# freeDSP.net
KiCad netlist of a schematic drawn in EAGLE
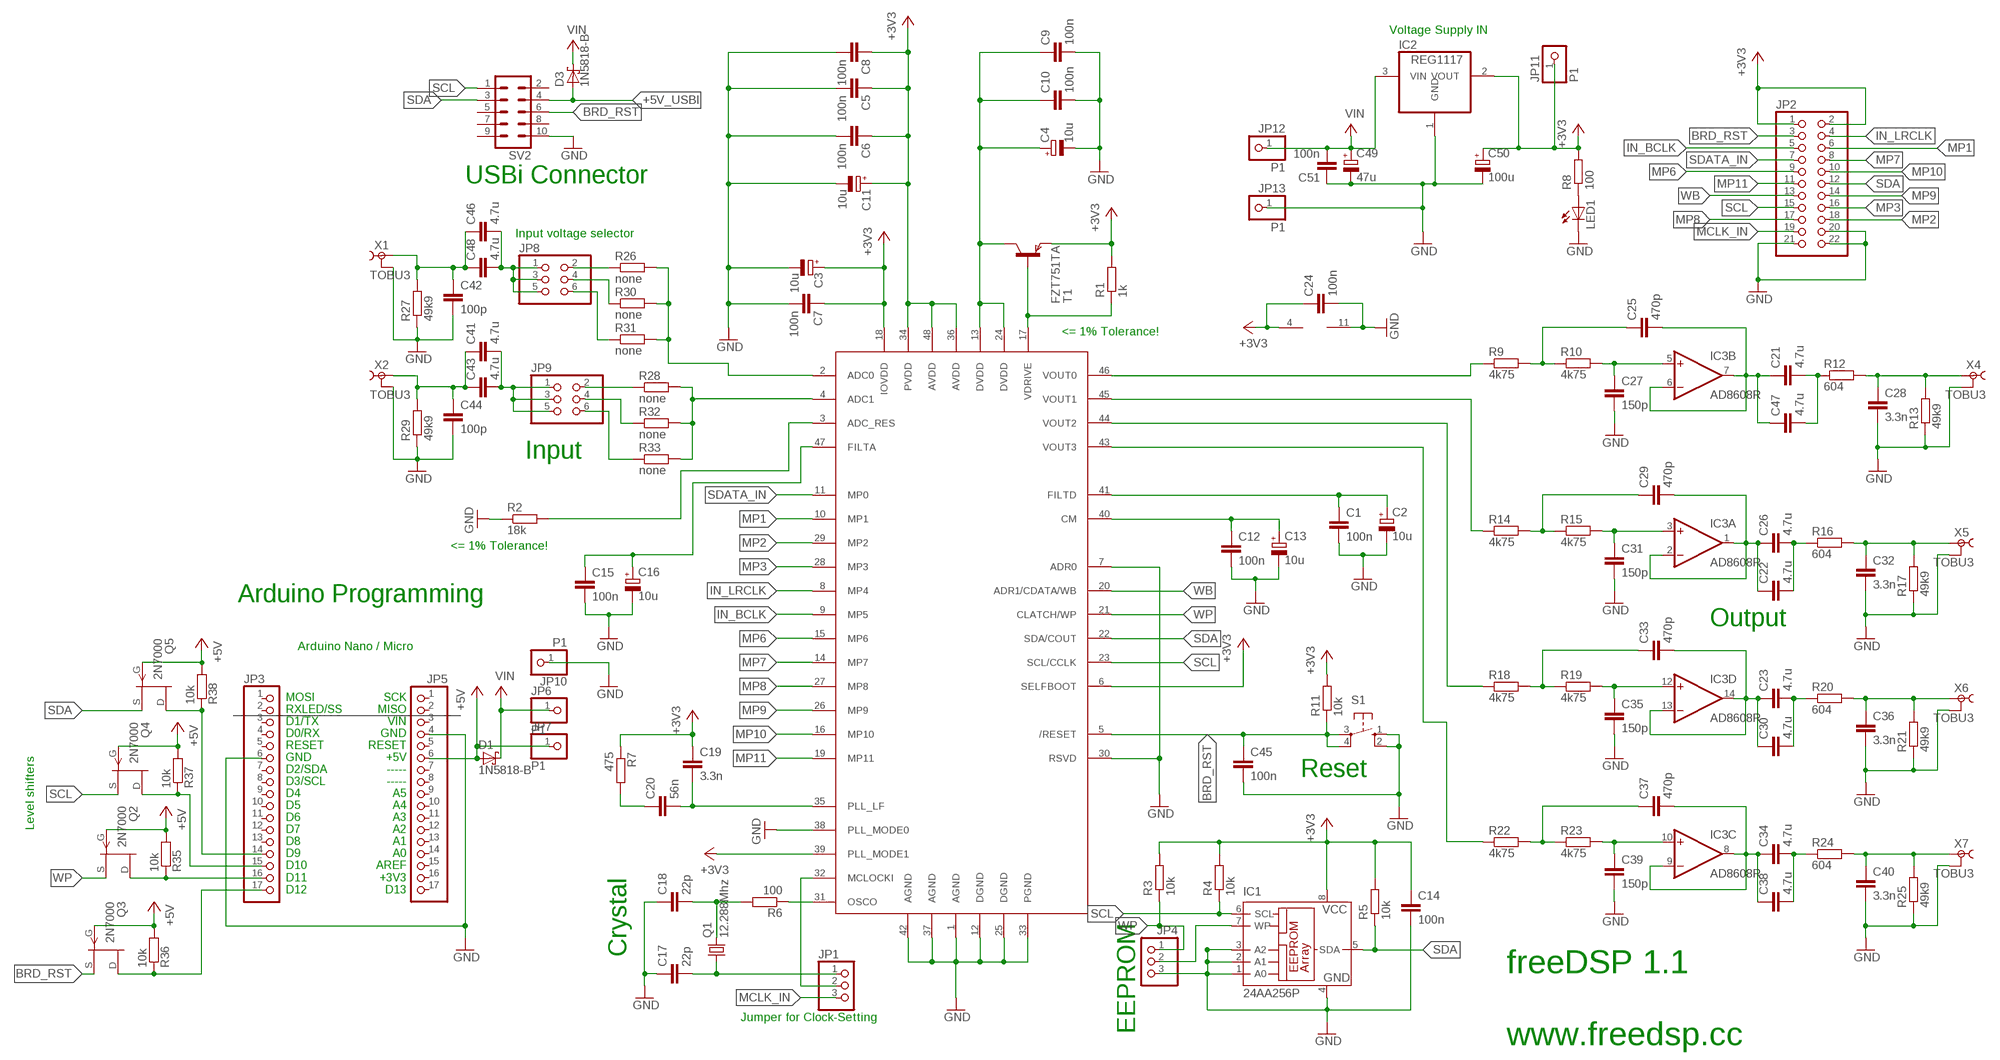
[diagram p0: schematic, sheet 1]

(export (version "E")
  (design (tool "Eeschema 10.0.6"))
  (components
    (comp (ref "C1")
      (value "100n")
      (footprint "eagle-import:C050-025X075")
      (libsource (lib "eagle-import") (part "resistor_C-EU050-025X075"))
    )
    (comp (ref "C2")
      (value "10u")
      (footprint "eagle-import:E1,8-4")
      (libsource (lib "eagle-import") (part "CPOL-EUE1.8-4"))
    )
    (comp (ref "C3")
      (value "10u")
      (footprint "eagle-import:E1,8-4")
      (libsource (lib "eagle-import") (part "CPOL-EUE1.8-4"))
    )
    (comp (ref "C4")
      (value "10u")
      (footprint "eagle-import:E1,8-4")
      (libsource (lib "eagle-import") (part "CPOL-EUE1.8-4"))
    )
    (comp (ref "C5")
      (value "100n")
      (footprint "eagle-import:C050-025X075")
      (libsource (lib "eagle-import") (part "resistor_C-EU050-025X075"))
    )
    (comp (ref "C6")
      (value "100n")
      (footprint "eagle-import:C050-025X075")
      (libsource (lib "eagle-import") (part "resistor_C-EU050-025X075"))
    )
    (comp (ref "C7")
      (value "100n")
      (footprint "eagle-import:C050-025X075")
      (libsource (lib "eagle-import") (part "resistor_C-EU050-025X075"))
    )
    (comp (ref "C8")
      (value "100n")
      (footprint "eagle-import:C050-025X075")
      (libsource (lib "eagle-import") (part "resistor_C-EU050-025X075"))
    )
    (comp (ref "C9")
      (value "100n")
      (footprint "eagle-import:C050-025X075")
      (libsource (lib "eagle-import") (part "resistor_C-EU050-025X075"))
    )
    (comp (ref "C10")
      (value "100n")
      (footprint "eagle-import:C050-025X075")
      (libsource (lib "eagle-import") (part "resistor_C-EU050-025X075"))
    )
    (comp (ref "C11")
      (value "10u")
      (footprint "eagle-import:E1,8-4")
      (libsource (lib "eagle-import") (part "CPOL-EUE1.8-4"))
    )
    (comp (ref "C12")
      (value "100n")
      (footprint "eagle-import:C050-025X075")
      (libsource (lib "eagle-import") (part "resistor_C-EU050-025X075"))
    )
    (comp (ref "C13")
      (value "10u")
      (footprint "eagle-import:E1,8-4")
      (libsource (lib "eagle-import") (part "CPOL-EUE1.8-4"))
    )
    (comp (ref "C14")
      (value "100n")
      (footprint "eagle-import:C050-025X075")
      (libsource (lib "eagle-import") (part "resistor_C-EU050-025X075"))
    )
    (comp (ref "C15")
      (value "100n")
      (footprint "eagle-import:C050-025X075")
      (libsource (lib "eagle-import") (part "resistor_C-EU050-025X075"))
    )
    (comp (ref "C16")
      (value "10u")
      (footprint "eagle-import:E1,8-4")
      (libsource (lib "eagle-import") (part "CPOL-EUE1.8-4"))
    )
    (comp (ref "C17")
      (value "22p")
      (footprint "eagle-import:C025-025X050")
      (libsource (lib "eagle-import") (part "C-EU025-025X050"))
    )
    (comp (ref "C18")
      (value "22p")
      (footprint "eagle-import:C025-025X050")
      (libsource (lib "eagle-import") (part "C-EU025-025X050"))
    )
    (comp (ref "C19")
      (value "3.3n")
      (footprint "eagle-import:C050-025X075")
      (libsource (lib "eagle-import") (part "resistor_C-EU050-025X075"))
    )
    (comp (ref "C20")
      (value "56n")
      (footprint "eagle-import:C050-025X075")
      (libsource (lib "eagle-import") (part "resistor_C-EU050-025X075"))
    )
    (comp (ref "C21")
      (value "4.7u")
      (footprint "eagle-import:C025-025X050")
      (libsource (lib "eagle-import") (part "resistor_C-EU025-025X050"))
    )
    (comp (ref "C22")
      (value "4.7u")
      (footprint "eagle-import:C025-025X050")
      (libsource (lib "eagle-import") (part "resistor_C-EU025-025X050"))
    )
    (comp (ref "C23")
      (value "4.7u")
      (footprint "eagle-import:C025-025X050")
      (libsource (lib "eagle-import") (part "resistor_C-EU025-025X050"))
    )
    (comp (ref "C24")
      (value "100n")
      (footprint "eagle-import:C050-025X075")
      (libsource (lib "eagle-import") (part "resistor_C-EU050-025X075"))
    )
    (comp (ref "C25")
      (value "470p")
      (footprint "eagle-import:C050-050X075")
      (libsource (lib "eagle-import") (part "C-EU050-050X075"))
    )
    (comp (ref "C26")
      (value "4.7u")
      (footprint "eagle-import:C025-025X050")
      (libsource (lib "eagle-import") (part "resistor_C-EU025-025X050"))
    )
    (comp (ref "C27")
      (value "150p")
      (footprint "eagle-import:C050-050X075")
      (libsource (lib "eagle-import") (part "resistor_C-EU050-050X075"))
    )
    (comp (ref "C28")
      (value "3.3n")
      (footprint "eagle-import:C050-025X075")
      (libsource (lib "eagle-import") (part "resistor_C-EU050-025X075"))
    )
    (comp (ref "C29")
      (value "470p")
      (footprint "eagle-import:C050-050X075")
      (libsource (lib "eagle-import") (part "C-EU050-050X075"))
    )
    (comp (ref "C30")
      (value "4.7u")
      (footprint "eagle-import:C025-025X050")
      (libsource (lib "eagle-import") (part "resistor_C-EU025-025X050"))
    )
    (comp (ref "C31")
      (value "150p")
      (footprint "eagle-import:C050-050X075")
      (libsource (lib "eagle-import") (part "resistor_C-EU050-050X075"))
    )
    (comp (ref "C32")
      (value "3.3n")
      (footprint "eagle-import:C050-025X075")
      (libsource (lib "eagle-import") (part "resistor_C-EU050-025X075"))
    )
    (comp (ref "C33")
      (value "470p")
      (footprint "eagle-import:C050-050X075")
      (libsource (lib "eagle-import") (part "C-EU050-050X075"))
    )
    (comp (ref "C34")
      (value "4.7u")
      (footprint "eagle-import:C025-025X050")
      (libsource (lib "eagle-import") (part "resistor_C-EU025-025X050"))
    )
    (comp (ref "C35")
      (value "150p")
      (footprint "eagle-import:C050-050X075")
      (libsource (lib "eagle-import") (part "resistor_C-EU050-050X075"))
    )
    (comp (ref "C36")
      (value "3.3n")
      (footprint "eagle-import:C050-025X075")
      (libsource (lib "eagle-import") (part "resistor_C-EU050-025X075"))
    )
    (comp (ref "C37")
      (value "470p")
      (footprint "eagle-import:C050-050X075")
      (libsource (lib "eagle-import") (part "C-EU050-050X075"))
    )
    (comp (ref "C38")
      (value "4.7u")
      (footprint "eagle-import:C025-025X050")
      (libsource (lib "eagle-import") (part "resistor_C-EU025-025X050"))
    )
    (comp (ref "C39")
      (value "150p")
      (footprint "eagle-import:C050-050X075")
      (libsource (lib "eagle-import") (part "resistor_C-EU050-050X075"))
    )
    (comp (ref "C40")
      (value "3.3n")
      (footprint "eagle-import:C050-025X075")
      (libsource (lib "eagle-import") (part "resistor_C-EU050-025X075"))
    )
    (comp (ref "C41")
      (value "4.7u")
      (footprint "eagle-import:C025-025X050")
      (libsource (lib "eagle-import") (part "resistor_C-EU025-025X050"))
    )
    (comp (ref "C42")
      (value "100p")
      (footprint "eagle-import:C025-025X050")
      (libsource (lib "eagle-import") (part "C-EU025-025X050"))
    )
    (comp (ref "C43")
      (value "4.7u")
      (footprint "eagle-import:C025-025X050")
      (libsource (lib "eagle-import") (part "resistor_C-EU025-025X050"))
    )
    (comp (ref "C44")
      (value "100p")
      (footprint "eagle-import:C025-025X050")
      (libsource (lib "eagle-import") (part "C-EU025-025X050"))
    )
    (comp (ref "C45")
      (value "100n")
      (footprint "eagle-import:C050-025X075")
      (libsource (lib "eagle-import") (part "resistor_C-EU050-025X075"))
    )
    (comp (ref "C46")
      (value "4.7u")
      (footprint "eagle-import:C025-025X050")
      (libsource (lib "eagle-import") (part "resistor_C-EU025-025X050"))
    )
    (comp (ref "C47")
      (value "4.7u")
      (footprint "eagle-import:C025-025X050")
      (libsource (lib "eagle-import") (part "resistor_C-EU025-025X050"))
    )
    (comp (ref "C48")
      (value "4.7u")
      (footprint "eagle-import:C025-025X050")
      (libsource (lib "eagle-import") (part "resistor_C-EU025-025X050"))
    )
    (comp (ref "C49")
      (value "47u")
      (footprint "eagle-import:E2,5-6")
      (libsource (lib "eagle-import") (part "CPOL-EUE2.5-6"))
    )
    (comp (ref "C50")
      (value "100u")
      (footprint "eagle-import:E2,5-6")
      (libsource (lib "eagle-import") (part "CPOL-EUE2.5-6"))
    )
    (comp (ref "C51")
      (value "100n")
      (footprint "eagle-import:C050-025X075")
      (libsource (lib "eagle-import") (part "resistor_C-EU050-025X075"))
    )
    (comp (ref "D1")
      (value "1N5818-B")
      (footprint "eagle-import:DO41-7.6")
      (libsource (lib "eagle-import") (part "1N5818-B"))
    )
    (comp (ref "D3")
      (value "1N5818-B")
      (footprint "eagle-import:DO41-7.6")
      (libsource (lib "eagle-import") (part "1N5818-B"))
    )
    (comp (ref "IC1")
      (value "24AA256P")
      (footprint "eagle-import:DIL8")
      (fields (field (name "MF") "MICROCHIP") (field (name "MPN") "24AA256-I/P"))
      (libsource (lib "eagle-import") (part "24PAA256"))
    )
    (comp (ref "IC2")
      (value "REG1117")
      (footprint "eagle-import:SOT223")
      (libsource (lib "eagle-import") (part "REG1117"))
    )
    (comp (ref "IC3")
      (value "AD8608R")
      (footprint "eagle-import:SO-14")
      (libsource (lib "eagle-import") (part "AD8608R"))
    )
    (comp (ref "JP1")
      (value "PINHD-1X3")
      (footprint "eagle-import:1X03")
      (libsource (lib "eagle-import") (part "PINHD-1X3"))
    )
    (comp (ref "JP2")
      (value "PINHD-2X11")
      (footprint "eagle-import:2X11")
      (libsource (lib "eagle-import") (part "PINHD-2X11"))
    )
    (comp (ref "JP3")
      (value "PINHD-1X17")
      (footprint "eagle-import:1X17")
      (libsource (lib "eagle-import") (part "PINHD-1X17"))
    )
    (comp (ref "JP4")
      (value "PINHD-1X3")
      (footprint "eagle-import:1X03")
      (libsource (lib "eagle-import") (part "PINHD-1X3"))
    )
    (comp (ref "JP5")
      (value "PINHD-1X17")
      (footprint "eagle-import:1X17")
      (libsource (lib "eagle-import") (part "PINHD-1X17"))
    )
    (comp (ref "JP6")
      (value "P1")
      (footprint "eagle-import:1X01")
      (libsource (lib "eagle-import") (part "PINHD-1X1"))
    )
    (comp (ref "JP7")
      (value "P1")
      (footprint "eagle-import:1X01")
      (libsource (lib "eagle-import") (part "PINHD-1X1"))
    )
    (comp (ref "JP8")
      (value "PINHD-2X3")
      (footprint "eagle-import:2X03")
      (libsource (lib "eagle-import") (part "PINHD-2X3"))
    )
    (comp (ref "JP9")
      (value "PINHD-2X3")
      (footprint "eagle-import:2X03")
      (libsource (lib "eagle-import") (part "PINHD-2X3"))
    )
    (comp (ref "JP10")
      (value "P1")
      (footprint "eagle-import:1X01")
      (libsource (lib "eagle-import") (part "PINHD-1X1"))
    )
    (comp (ref "JP11")
      (value "P1")
      (footprint "eagle-import:1X01")
      (libsource (lib "eagle-import") (part "PINHD-1X1"))
    )
    (comp (ref "JP12")
      (value "P1")
      (footprint "eagle-import:1X01")
      (libsource (lib "eagle-import") (part "PINHD-1X1"))
    )
    (comp (ref "JP13")
      (value "P1")
      (footprint "eagle-import:1X01")
      (libsource (lib "eagle-import") (part "PINHD-1X1"))
    )
    (comp (ref "LED1")
      (value "LED3MM")
      (footprint "eagle-import:LED3MM")
      (libsource (lib "eagle-import") (part "LED3MM"))
    )
    (comp (ref "Q1")
      (value "12.288Mhz")
      (footprint "eagle-import:SM49")
      (libsource (lib "eagle-import") (part "CRYSTALSM49"))
    )
    (comp (ref "Q2")
      (value "2N7000")
      (footprint "eagle-import:TO92")
      (libsource (lib "eagle-import") (part "2N3819"))
    )
    (comp (ref "Q3")
      (value "2N7000")
      (footprint "eagle-import:TO92")
      (libsource (lib "eagle-import") (part "2N3819"))
    )
    (comp (ref "Q4")
      (value "2N7000")
      (footprint "eagle-import:TO92")
      (libsource (lib "eagle-import") (part "2N3819"))
    )
    (comp (ref "Q5")
      (value "2N7000")
      (footprint "eagle-import:TO92")
      (libsource (lib "eagle-import") (part "2N3819"))
    )
    (comp (ref "R1")
      (value "1k")
      (footprint "eagle-import:0204_7")
      (libsource (lib "eagle-import") (part "R-EU_0204/7"))
    )
    (comp (ref "R2")
      (value "18k")
      (footprint "eagle-import:0204_7")
      (libsource (lib "eagle-import") (part "R-EU_0204/7"))
    )
    (comp (ref "R3")
      (value "10k")
      (footprint "eagle-import:0204_7")
      (libsource (lib "eagle-import") (part "R-EU_0204/7"))
    )
    (comp (ref "R4")
      (value "10k")
      (footprint "eagle-import:0204_7")
      (libsource (lib "eagle-import") (part "R-EU_0204/7"))
    )
    (comp (ref "R5")
      (value "10k")
      (footprint "eagle-import:0204_7")
      (libsource (lib "eagle-import") (part "R-EU_0204/7"))
    )
    (comp (ref "R6")
      (value "100")
      (footprint "eagle-import:0204_7")
      (libsource (lib "eagle-import") (part "R-EU_0204/7"))
    )
    (comp (ref "R7")
      (value "475")
      (footprint "eagle-import:0204_7")
      (libsource (lib "eagle-import") (part "R-EU_0204/7"))
    )
    (comp (ref "R8")
      (value "100")
      (footprint "eagle-import:0204_7")
      (libsource (lib "eagle-import") (part "R-EU_0204/7"))
    )
    (comp (ref "R9")
      (value "4k75")
      (footprint "eagle-import:0204_7")
      (libsource (lib "eagle-import") (part "R-EU_0204/7"))
    )
    (comp (ref "R10")
      (value "4k75")
      (footprint "eagle-import:0204_7")
      (libsource (lib "eagle-import") (part "R-EU_0204/7"))
    )
    (comp (ref "R11")
      (value "10k")
      (footprint "eagle-import:0204_7")
      (libsource (lib "eagle-import") (part "R-EU_0204/7"))
    )
    (comp (ref "R12")
      (value "604")
      (footprint "eagle-import:0204_7")
      (libsource (lib "eagle-import") (part "R-EU_0204/7"))
    )
    (comp (ref "R13")
      (value "49k9")
      (footprint "eagle-import:0204_7")
      (libsource (lib "eagle-import") (part "R-EU_0204/7"))
    )
    (comp (ref "R14")
      (value "4k75")
      (footprint "eagle-import:0204_7")
      (libsource (lib "eagle-import") (part "R-EU_0204/7"))
    )
    (comp (ref "R15")
      (value "4k75")
      (footprint "eagle-import:0204_7")
      (libsource (lib "eagle-import") (part "R-EU_0204/7"))
    )
    (comp (ref "R16")
      (value "604")
      (footprint "eagle-import:0204_7")
      (libsource (lib "eagle-import") (part "R-EU_0204/7"))
    )
    (comp (ref "R17")
      (value "49k9")
      (footprint "eagle-import:0204_7")
      (libsource (lib "eagle-import") (part "R-EU_0204/7"))
    )
    (comp (ref "R18")
      (value "4k75")
      (footprint "eagle-import:0204_7")
      (libsource (lib "eagle-import") (part "R-EU_0204/7"))
    )
    (comp (ref "R19")
      (value "4k75")
      (footprint "eagle-import:0204_7")
      (libsource (lib "eagle-import") (part "R-EU_0204/7"))
    )
    (comp (ref "R20")
      (value "604")
      (footprint "eagle-import:0204_7")
      (libsource (lib "eagle-import") (part "R-EU_0204/7"))
    )
    (comp (ref "R21")
      (value "49k9")
      (footprint "eagle-import:0204_7")
      (libsource (lib "eagle-import") (part "R-EU_0204/7"))
    )
    (comp (ref "R22")
      (value "4k75")
      (footprint "eagle-import:0204_7")
      (libsource (lib "eagle-import") (part "R-EU_0204/7"))
    )
    (comp (ref "R23")
      (value "4k75")
      (footprint "eagle-import:0204_7")
      (libsource (lib "eagle-import") (part "R-EU_0204/7"))
    )
    (comp (ref "R24")
      (value "604")
      (footprint "eagle-import:0204_7")
      (libsource (lib "eagle-import") (part "R-EU_0204/7"))
    )
    (comp (ref "R25")
      (value "49k9")
      (footprint "eagle-import:0204_7")
      (libsource (lib "eagle-import") (part "R-EU_0204/7"))
    )
    (comp (ref "R26")
      (value "none")
      (footprint "eagle-import:0204_7")
      (libsource (lib "eagle-import") (part "R-EU_0204/7"))
    )
    (comp (ref "R27")
      (value "49k9")
      (footprint "eagle-import:0204_7")
      (libsource (lib "eagle-import") (part "R-EU_0204/7"))
    )
    (comp (ref "R28")
      (value "none")
      (footprint "eagle-import:0204_7")
      (libsource (lib "eagle-import") (part "R-EU_0204/7"))
    )
    (comp (ref "R29")
      (value "49k9")
      (footprint "eagle-import:0204_7")
      (libsource (lib "eagle-import") (part "R-EU_0204/7"))
    )
    (comp (ref "R30")
      (value "none")
      (footprint "eagle-import:0204_7")
      (libsource (lib "eagle-import") (part "R-EU_0204/7"))
    )
    (comp (ref "R31")
      (value "none")
      (footprint "eagle-import:0204_7")
      (libsource (lib "eagle-import") (part "R-EU_0204/7"))
    )
    (comp (ref "R32")
      (value "none")
      (footprint "eagle-import:0204_7")
      (libsource (lib "eagle-import") (part "R-EU_0204/7"))
    )
    (comp (ref "R33")
      (value "none")
      (footprint "eagle-import:0204_7")
      (libsource (lib "eagle-import") (part "R-EU_0204/7"))
    )
    (comp (ref "R35")
      (value "10k")
      (footprint "eagle-import:0204_7")
      (libsource (lib "eagle-import") (part "R-EU_0204/7"))
    )
    (comp (ref "R36")
      (value "10k")
      (footprint "eagle-import:0204_7")
      (libsource (lib "eagle-import") (part "R-EU_0204/7"))
    )
    (comp (ref "R37")
      (value "10k")
      (footprint "eagle-import:0204_7")
      (libsource (lib "eagle-import") (part "R-EU_0204/7"))
    )
    (comp (ref "R38")
      (value "10k")
      (footprint "eagle-import:0204_7")
      (libsource (lib "eagle-import") (part "R-EU_0204/7"))
    )
    (comp (ref "S1")
      (value "10-XX")
      (footprint "eagle-import:B3F-10XX")
      (fields (field (name "MPN") "B3F-1000"))
      (libsource (lib "eagle-import") (part "10-XX"))
    )
    (comp (ref "SV2")
      (value "ML10")
      (footprint "eagle-import:ML10")
      (libsource (lib "eagle-import") (part "ML10"))
    )
    (comp (ref "T1")
      (value "FZT751TA")
      (footprint "eagle-import:SOT223")
      (fields (field (name "MPN") "FZT789A"))
      (libsource (lib "eagle-import") (part "FZT789A"))
    )
    (comp (ref "U$1")
      (value "ADAU1701")
      (footprint "eagle-import:LQFP-48")
      (libsource (lib "eagle-import") (part "ADAU1701"))
    )
    (comp (ref "X1")
      (value "TOBU3")
      (footprint "eagle-import:TOBU3")
      (fields (field (name "MF") "FARNELL") (field (name "MPN") "TOBU 3"))
      (libsource (lib "eagle-import") (part "TOBU3"))
    )
    (comp (ref "X2")
      (value "TOBU3")
      (footprint "eagle-import:TOBU3")
      (fields (field (name "MF") "FARNELL") (field (name "MPN") "TOBU 3"))
      (libsource (lib "eagle-import") (part "TOBU3"))
    )
    (comp (ref "X4")
      (value "TOBU3")
      (footprint "eagle-import:TOBU3")
      (fields (field (name "MF") "FARNELL") (field (name "MPN") "TOBU 3"))
      (libsource (lib "eagle-import") (part "TOBU3"))
    )
    (comp (ref "X5")
      (value "TOBU3")
      (footprint "eagle-import:TOBU3")
      (fields (field (name "MF") "FARNELL") (field (name "MPN") "TOBU 3"))
      (libsource (lib "eagle-import") (part "TOBU3"))
    )
    (comp (ref "X6")
      (value "TOBU3")
      (footprint "eagle-import:TOBU3")
      (fields (field (name "MF") "FARNELL") (field (name "MPN") "TOBU 3"))
      (libsource (lib "eagle-import") (part "TOBU3"))
    )
    (comp (ref "X7")
      (value "TOBU3")
      (footprint "eagle-import:TOBU3")
      (fields (field (name "MF") "FARNELL") (field (name "MPN") "TOBU 3"))
      (libsource (lib "eagle-import") (part "TOBU3"))
    )
  )
  (nets
    (net (code "1") (name "+3V3") (class "Default")
      (node (ref "C11") (pin "+") (pinfunction "+_+") (pintype "passive"))
      (node (ref "C14") (pin "1") (pinfunction "1_1") (pintype "passive"))
      (node (ref "C19") (pin "1") (pinfunction "1_1") (pintype "passive"))
      (node (ref "C24") (pin "1") (pinfunction "1_1") (pintype "passive"))
      (node (ref "C3") (pin "+") (pinfunction "+_+") (pintype "passive"))
      (node (ref "C5") (pin "1") (pinfunction "1_1") (pintype "passive"))
      (node (ref "C50") (pin "+") (pinfunction "+_+") (pintype "passive"))
      (node (ref "C6") (pin "1") (pinfunction "1_1") (pintype "passive"))
      (node (ref "C7") (pin "1") (pinfunction "1_1") (pintype "passive"))
      (node (ref "C8") (pin "1") (pinfunction "1_1") (pintype "passive"))
      (node (ref "IC1") (pin "8") (pinfunction "VCC_8") (pintype "power_in"))
      (node (ref "IC2") (pin "2") (pinfunction "VOUT_2") (pintype "output"))
      (node (ref "IC3") (pin "4") (pinfunction "V+_4") (pintype "power_in"))
      (node (ref "JP11") (pin "1") (pinfunction "1_1") (pintype "passive"))
      (node (ref "JP2") (pin "1") (pinfunction "1_1") (pintype "passive"))
      (node (ref "JP2") (pin "2") (pinfunction "2_2") (pintype "passive"))
      (node (ref "R1") (pin "2") (pinfunction "2_2") (pintype "passive"))
      (node (ref "R11") (pin "2") (pinfunction "2_2") (pintype "passive"))
      (node (ref "R3") (pin "2") (pinfunction "2_2") (pintype "passive"))
      (node (ref "R4") (pin "2") (pinfunction "2_2") (pintype "passive"))
      (node (ref "R5") (pin "2") (pinfunction "2_2") (pintype "passive"))
      (node (ref "R7") (pin "1") (pinfunction "1_1") (pintype "passive"))
      (node (ref "R8") (pin "2") (pinfunction "2_2") (pintype "passive"))
      (node (ref "T1") (pin "3") (pinfunction "E_3") (pintype "passive"))
      (node (ref "U$1") (pin "18") (pinfunction "IOVDD_18") (pintype "bidirectional"))
      (node (ref "U$1") (pin "34") (pinfunction "PVDD_34") (pintype "bidirectional"))
      (node (ref "U$1") (pin "36") (pinfunction "AVDD_36") (pintype "bidirectional"))
      (node (ref "U$1") (pin "39") (pinfunction "PLL_MODE1_39") (pintype "bidirectional"))
      (node (ref "U$1") (pin "48") (pinfunction "AVDD_48") (pintype "bidirectional"))
      (node (ref "U$1") (pin "6") (pinfunction "SELFBOOT_6") (pintype "bidirectional"))
    )
    (net (code "2") (name "+5V") (class "Default")
      (node (ref "D1") (pin "A") (pinfunction "A_A") (pintype "passive"))
      (node (ref "JP5") (pin "6") (pinfunction "6_6") (pintype "passive"))
      (node (ref "JP7") (pin "1") (pinfunction "1_1") (pintype "passive"))
      (node (ref "Q2") (pin "2") (pinfunction "G_2") (pintype "passive"))
      (node (ref "Q3") (pin "2") (pinfunction "G_2") (pintype "passive"))
      (node (ref "Q4") (pin "2") (pinfunction "G_2") (pintype "passive"))
      (node (ref "Q5") (pin "2") (pinfunction "G_2") (pintype "passive"))
      (node (ref "R35") (pin "2") (pinfunction "2_2") (pintype "passive"))
      (node (ref "R36") (pin "2") (pinfunction "2_2") (pintype "passive"))
      (node (ref "R37") (pin "2") (pinfunction "2_2") (pintype "passive"))
      (node (ref "R38") (pin "2") (pinfunction "2_2") (pintype "passive"))
    )
    (net (code "3") (name "+5V_USBI") (class "Default")
      (node (ref "D3") (pin "A") (pinfunction "A_A") (pintype "passive"))
      (node (ref "SV2") (pin "4") (pinfunction "4_4") (pintype "passive"))
    )
    (net (code "4") (name "BRD_RST") (class "Default")
      (node (ref "C45") (pin "1") (pinfunction "1_1") (pintype "passive"))
      (node (ref "JP2") (pin "3") (pinfunction "3_3") (pintype "passive"))
      (node (ref "Q3") (pin "3") (pinfunction "S_3") (pintype "passive"))
      (node (ref "R11") (pin "1") (pinfunction "1_1") (pintype "passive"))
      (node (ref "S1") (pin "3") (pinfunction "P_3") (pintype "passive"))
      (node (ref "S1") (pin "4") (pinfunction "P1_4") (pintype "passive"))
      (node (ref "SV2") (pin "6") (pinfunction "6_6") (pintype "passive"))
      (node (ref "U$1") (pin "5") (pinfunction "/RESET_5") (pintype "bidirectional"))
    )
    (net (code "5") (name "GND") (class "Default")
      (node (ref "C1") (pin "2") (pinfunction "2_2") (pintype "passive"))
      (node (ref "C10") (pin "2") (pinfunction "2_2") (pintype "passive"))
      (node (ref "C11") (pin "-") (pinfunction "-_-") (pintype "passive"))
      (node (ref "C12") (pin "2") (pinfunction "2_2") (pintype "passive"))
      (node (ref "C13") (pin "-") (pinfunction "-_-") (pintype "passive"))
      (node (ref "C14") (pin "2") (pinfunction "2_2") (pintype "passive"))
      (node (ref "C15") (pin "2") (pinfunction "2_2") (pintype "passive"))
      (node (ref "C16") (pin "-") (pinfunction "-_-") (pintype "passive"))
      (node (ref "C17") (pin "1") (pinfunction "1_1") (pintype "passive"))
      (node (ref "C18") (pin "1") (pinfunction "1_1") (pintype "passive"))
      (node (ref "C2") (pin "-") (pinfunction "-_-") (pintype "passive"))
      (node (ref "C24") (pin "2") (pinfunction "2_2") (pintype "passive"))
      (node (ref "C27") (pin "2") (pinfunction "2_2") (pintype "passive"))
      (node (ref "C28") (pin "2") (pinfunction "2_2") (pintype "passive"))
      (node (ref "C3") (pin "-") (pinfunction "-_-") (pintype "passive"))
      (node (ref "C31") (pin "2") (pinfunction "2_2") (pintype "passive"))
      (node (ref "C32") (pin "2") (pinfunction "2_2") (pintype "passive"))
      (node (ref "C35") (pin "2") (pinfunction "2_2") (pintype "passive"))
      (node (ref "C36") (pin "2") (pinfunction "2_2") (pintype "passive"))
      (node (ref "C39") (pin "2") (pinfunction "2_2") (pintype "passive"))
      (node (ref "C4") (pin "-") (pinfunction "-_-") (pintype "passive"))
      (node (ref "C40") (pin "2") (pinfunction "2_2") (pintype "passive"))
      (node (ref "C42") (pin "2") (pinfunction "2_2") (pintype "passive"))
      (node (ref "C44") (pin "2") (pinfunction "2_2") (pintype "passive"))
      (node (ref "C45") (pin "2") (pinfunction "2_2") (pintype "passive"))
      (node (ref "C49") (pin "-") (pinfunction "-_-") (pintype "passive"))
      (node (ref "C5") (pin "2") (pinfunction "2_2") (pintype "passive"))
      (node (ref "C50") (pin "-") (pinfunction "-_-") (pintype "passive"))
      (node (ref "C51") (pin "1") (pinfunction "1_1") (pintype "passive"))
      (node (ref "C6") (pin "2") (pinfunction "2_2") (pintype "passive"))
      (node (ref "C7") (pin "2") (pinfunction "2_2") (pintype "passive"))
      (node (ref "C8") (pin "2") (pinfunction "2_2") (pintype "passive"))
      (node (ref "C9") (pin "2") (pinfunction "2_2") (pintype "passive"))
      (node (ref "IC1") (pin "1") (pinfunction "A0_1") (pintype "input"))
      (node (ref "IC1") (pin "2") (pinfunction "A1_2") (pintype "input"))
      (node (ref "IC1") (pin "3") (pinfunction "A2_3") (pintype "input"))
      (node (ref "IC1") (pin "4") (pinfunction "GND_4") (pintype "power_in"))
      (node (ref "IC2") (pin "1") (pinfunction "GND_1") (pintype "power_in"))
      (node (ref "IC3") (pin "11") (pinfunction "V-_11") (pintype "power_in"))
      (node (ref "JP10") (pin "1") (pinfunction "1_1") (pintype "passive"))
      (node (ref "JP13") (pin "1") (pinfunction "1_1") (pintype "passive"))
      (node (ref "JP2") (pin "20") (pinfunction "20_20") (pintype "passive"))
      (node (ref "JP2") (pin "21") (pinfunction "21_21") (pintype "passive"))
      (node (ref "JP2") (pin "22") (pinfunction "22_22") (pintype "passive"))
      (node (ref "JP3") (pin "6") (pinfunction "6_6") (pintype "passive"))
      (node (ref "JP4") (pin "3") (pinfunction "3_3") (pintype "passive"))
      (node (ref "JP5") (pin "4") (pinfunction "4_4") (pintype "passive"))
      (node (ref "LED1") (pin "K") (pinfunction "C_K") (pintype "passive"))
      (node (ref "R13") (pin "1") (pinfunction "1_1") (pintype "passive"))
      (node (ref "R17") (pin "1") (pinfunction "1_1") (pintype "passive"))
      (node (ref "R2") (pin "1") (pinfunction "1_1") (pintype "passive"))
      (node (ref "R21") (pin "1") (pinfunction "1_1") (pintype "passive"))
      (node (ref "R25") (pin "1") (pinfunction "1_1") (pintype "passive"))
      (node (ref "R27") (pin "1") (pinfunction "1_1") (pintype "passive"))
      (node (ref "R29") (pin "1") (pinfunction "1_1") (pintype "passive"))
      (node (ref "S1") (pin "1") (pinfunction "S_1") (pintype "passive"))
      (node (ref "S1") (pin "2") (pinfunction "S1_2") (pintype "passive"))
      (node (ref "SV2") (pin "10") (pinfunction "10_10") (pintype "passive"))
      (node (ref "U$1") (pin "1") (pinfunction "AGND_1") (pintype "bidirectional"))
      (node (ref "U$1") (pin "12") (pinfunction "DGND_12") (pintype "bidirectional"))
      (node (ref "U$1") (pin "25") (pinfunction "DGND_25") (pintype "bidirectional"))
      (node (ref "U$1") (pin "30") (pinfunction "RSVD_30") (pintype "bidirectional"))
      (node (ref "U$1") (pin "33") (pinfunction "PGND_33") (pintype "bidirectional"))
      (node (ref "U$1") (pin "37") (pinfunction "AGND_37") (pintype "bidirectional"))
      (node (ref "U$1") (pin "38") (pinfunction "PLL_MODE0_38") (pintype "bidirectional"))
      (node (ref "U$1") (pin "42") (pinfunction "AGND_42") (pintype "bidirectional"))
      (node (ref "U$1") (pin "7") (pinfunction "ADR0_7") (pintype "bidirectional"))
      (node (ref "X1") (pin "2") (pinfunction "2_2") (pintype "passive"))
      (node (ref "X1") (pin "2@1") (pinfunction "2_2@1") (pintype "passive"))
      (node (ref "X1") (pin "2@2") (pinfunction "2_2@2") (pintype "passive"))
      (node (ref "X2") (pin "2") (pinfunction "2_2") (pintype "passive"))
      (node (ref "X2") (pin "2@1") (pinfunction "2_2@1") (pintype "passive"))
      (node (ref "X2") (pin "2@2") (pinfunction "2_2@2") (pintype "passive"))
      (node (ref "X4") (pin "2") (pinfunction "2_2") (pintype "passive"))
      (node (ref "X4") (pin "2@1") (pinfunction "2_2@1") (pintype "passive"))
      (node (ref "X4") (pin "2@2") (pinfunction "2_2@2") (pintype "passive"))
      (node (ref "X5") (pin "2") (pinfunction "2_2") (pintype "passive"))
      (node (ref "X5") (pin "2@1") (pinfunction "2_2@1") (pintype "passive"))
      (node (ref "X5") (pin "2@2") (pinfunction "2_2@2") (pintype "passive"))
      (node (ref "X6") (pin "2") (pinfunction "2_2") (pintype "passive"))
      (node (ref "X6") (pin "2@1") (pinfunction "2_2@1") (pintype "passive"))
      (node (ref "X6") (pin "2@2") (pinfunction "2_2@2") (pintype "passive"))
      (node (ref "X7") (pin "2") (pinfunction "2_2") (pintype "passive"))
      (node (ref "X7") (pin "2@1") (pinfunction "2_2@1") (pintype "passive"))
      (node (ref "X7") (pin "2@2") (pinfunction "2_2@2") (pintype "passive"))
    )
    (net (code "6") (name "IN_BCLK") (class "Default")
      (node (ref "JP2") (pin "5") (pinfunction "5_5") (pintype "passive"))
      (node (ref "U$1") (pin "9") (pinfunction "MP5_9") (pintype "bidirectional"))
    )
    (net (code "7") (name "IN_LRCLK") (class "Default")
      (node (ref "JP2") (pin "4") (pinfunction "4_4") (pintype "passive"))
      (node (ref "U$1") (pin "8") (pinfunction "MP4_8") (pintype "bidirectional"))
    )
    (net (code "8") (name "MCLK_IN") (class "Default")
      (node (ref "JP1") (pin "3") (pinfunction "3_3") (pintype "passive"))
      (node (ref "JP2") (pin "19") (pinfunction "19_19") (pintype "passive"))
    )
    (net (code "9") (name "MP1") (class "Default")
      (node (ref "JP2") (pin "6") (pinfunction "6_6") (pintype "passive"))
      (node (ref "U$1") (pin "10") (pinfunction "MP1_10") (pintype "bidirectional"))
    )
    (net (code "10") (name "MP2") (class "Default")
      (node (ref "JP2") (pin "18") (pinfunction "18_18") (pintype "passive"))
      (node (ref "U$1") (pin "29") (pinfunction "MP2_29") (pintype "bidirectional"))
    )
    (net (code "11") (name "MP3") (class "Default")
      (node (ref "JP2") (pin "16") (pinfunction "16_16") (pintype "passive"))
      (node (ref "U$1") (pin "28") (pinfunction "MP3_28") (pintype "bidirectional"))
    )
    (net (code "12") (name "MP6") (class "Default")
      (node (ref "JP2") (pin "9") (pinfunction "9_9") (pintype "passive"))
      (node (ref "U$1") (pin "15") (pinfunction "MP6_15") (pintype "bidirectional"))
    )
    (net (code "13") (name "MP7") (class "Default")
      (node (ref "JP2") (pin "8") (pinfunction "8_8") (pintype "passive"))
      (node (ref "U$1") (pin "14") (pinfunction "MP7_14") (pintype "bidirectional"))
    )
    (net (code "14") (name "MP8") (class "Default")
      (node (ref "JP2") (pin "17") (pinfunction "17_17") (pintype "passive"))
      (node (ref "U$1") (pin "27") (pinfunction "MP8_27") (pintype "bidirectional"))
    )
    (net (code "15") (name "MP9") (class "Default")
      (node (ref "JP2") (pin "14") (pinfunction "14_14") (pintype "passive"))
      (node (ref "U$1") (pin "26") (pinfunction "MP9_26") (pintype "bidirectional"))
    )
    (net (code "16") (name "MP10") (class "Default")
      (node (ref "JP2") (pin "10") (pinfunction "10_10") (pintype "passive"))
      (node (ref "U$1") (pin "16") (pinfunction "MP10_16") (pintype "bidirectional"))
    )
    (net (code "17") (name "MP11") (class "Default")
      (node (ref "JP2") (pin "11") (pinfunction "11_11") (pintype "passive"))
      (node (ref "U$1") (pin "19") (pinfunction "MP11_19") (pintype "bidirectional"))
    )
    (net (code "18") (name "Net-(C10-Pad1)") (class "Default")
      (node (ref "C10") (pin "1") (pinfunction "1_1") (pintype "passive"))
      (node (ref "C4") (pin "+") (pinfunction "+_+") (pintype "passive"))
      (node (ref "C9") (pin "1") (pinfunction "1_1") (pintype "passive"))
      (node (ref "T1") (pin "2") (pinfunction "C_2") (pintype "passive"))
      (node (ref "T1") (pin "4") (pinfunction "C_4") (pintype "passive"))
      (node (ref "U$1") (pin "13") (pinfunction "DVDD_13") (pintype "bidirectional"))
      (node (ref "U$1") (pin "24") (pinfunction "DVDD_24") (pintype "bidirectional"))
    )
    (net (code "19") (name "Net-(C17-Pad2)") (class "Default")
      (node (ref "C17") (pin "2") (pinfunction "2_2") (pintype "passive"))
      (node (ref "JP1") (pin "1") (pinfunction "1_1") (pintype "passive"))
      (node (ref "Q1") (pin "1") (pinfunction "1_1") (pintype "passive"))
    )
    (net (code "20") (name "Net-(C18-Pad2)") (class "Default")
      (node (ref "C18") (pin "2") (pinfunction "2_2") (pintype "passive"))
      (node (ref "Q1") (pin "2") (pinfunction "2_2") (pintype "passive"))
      (node (ref "R6") (pin "2") (pinfunction "2_2") (pintype "passive"))
    )
    (net (code "21") (name "Net-(C20-Pad1)") (class "Default")
      (node (ref "C20") (pin "1") (pinfunction "1_1") (pintype "passive"))
      (node (ref "R7") (pin "2") (pinfunction "2_2") (pintype "passive"))
    )
    (net (code "22") (name "Net-(C21-Pad2)") (class "Default")
      (node (ref "C21") (pin "2") (pinfunction "2_2") (pintype "passive"))
      (node (ref "C47") (pin "2") (pinfunction "2_2") (pintype "passive"))
      (node (ref "R12") (pin "1") (pinfunction "1_1") (pintype "passive"))
    )
    (net (code "23") (name "Net-(C22-Pad2)") (class "Default")
      (node (ref "C22") (pin "2") (pinfunction "2_2") (pintype "passive"))
      (node (ref "C26") (pin "2") (pinfunction "2_2") (pintype "passive"))
      (node (ref "R16") (pin "1") (pinfunction "1_1") (pintype "passive"))
    )
    (net (code "24") (name "Net-(C23-Pad2)") (class "Default")
      (node (ref "C23") (pin "2") (pinfunction "2_2") (pintype "passive"))
      (node (ref "C30") (pin "2") (pinfunction "2_2") (pintype "passive"))
      (node (ref "R20") (pin "1") (pinfunction "1_1") (pintype "passive"))
    )
    (net (code "25") (name "Net-(C25-Pad1)") (class "Default")
      (node (ref "C25") (pin "1") (pinfunction "1_1") (pintype "passive"))
      (node (ref "R10") (pin "1") (pinfunction "1_1") (pintype "passive"))
      (node (ref "R9") (pin "2") (pinfunction "2_2") (pintype "passive"))
    )
    (net (code "26") (name "Net-(C28-Pad1)") (class "Default")
      (node (ref "C28") (pin "1") (pinfunction "1_1") (pintype "passive"))
      (node (ref "R12") (pin "2") (pinfunction "2_2") (pintype "passive"))
      (node (ref "R13") (pin "2") (pinfunction "2_2") (pintype "passive"))
      (node (ref "X4") (pin "1") (pinfunction "1_1") (pintype "passive"))
    )
    (net (code "27") (name "Net-(C29-Pad1)") (class "Default")
      (node (ref "C29") (pin "1") (pinfunction "1_1") (pintype "passive"))
      (node (ref "R14") (pin "2") (pinfunction "2_2") (pintype "passive"))
      (node (ref "R15") (pin "1") (pinfunction "1_1") (pintype "passive"))
    )
    (net (code "28") (name "Net-(C32-Pad1)") (class "Default")
      (node (ref "C32") (pin "1") (pinfunction "1_1") (pintype "passive"))
      (node (ref "R16") (pin "2") (pinfunction "2_2") (pintype "passive"))
      (node (ref "R17") (pin "2") (pinfunction "2_2") (pintype "passive"))
      (node (ref "X5") (pin "1") (pinfunction "1_1") (pintype "passive"))
    )
    (net (code "29") (name "Net-(C33-Pad1)") (class "Default")
      (node (ref "C33") (pin "1") (pinfunction "1_1") (pintype "passive"))
      (node (ref "R18") (pin "2") (pinfunction "2_2") (pintype "passive"))
      (node (ref "R19") (pin "1") (pinfunction "1_1") (pintype "passive"))
    )
    (net (code "30") (name "Net-(C34-Pad2)") (class "Default")
      (node (ref "C34") (pin "2") (pinfunction "2_2") (pintype "passive"))
      (node (ref "C38") (pin "2") (pinfunction "2_2") (pintype "passive"))
      (node (ref "R24") (pin "1") (pinfunction "1_1") (pintype "passive"))
    )
    (net (code "31") (name "Net-(C36-Pad1)") (class "Default")
      (node (ref "C36") (pin "1") (pinfunction "1_1") (pintype "passive"))
      (node (ref "R20") (pin "2") (pinfunction "2_2") (pintype "passive"))
      (node (ref "R21") (pin "2") (pinfunction "2_2") (pintype "passive"))
      (node (ref "X6") (pin "1") (pinfunction "1_1") (pintype "passive"))
    )
    (net (code "32") (name "Net-(C37-Pad1)") (class "Default")
      (node (ref "C37") (pin "1") (pinfunction "1_1") (pintype "passive"))
      (node (ref "R22") (pin "2") (pinfunction "2_2") (pintype "passive"))
      (node (ref "R23") (pin "1") (pinfunction "1_1") (pintype "passive"))
    )
    (net (code "33") (name "Net-(C40-Pad1)") (class "Default")
      (node (ref "C40") (pin "1") (pinfunction "1_1") (pintype "passive"))
      (node (ref "R24") (pin "2") (pinfunction "2_2") (pintype "passive"))
      (node (ref "R25") (pin "2") (pinfunction "2_2") (pintype "passive"))
      (node (ref "X7") (pin "1") (pinfunction "1_1") (pintype "passive"))
    )
    (net (code "34") (name "Net-(C41-Pad1)") (class "Default")
      (node (ref "C41") (pin "1") (pinfunction "1_1") (pintype "passive"))
      (node (ref "C43") (pin "1") (pinfunction "1_1") (pintype "passive"))
      (node (ref "C44") (pin "1") (pinfunction "1_1") (pintype "passive"))
      (node (ref "R29") (pin "2") (pinfunction "2_2") (pintype "passive"))
      (node (ref "X2") (pin "1") (pinfunction "1_1") (pintype "passive"))
    )
    (net (code "35") (name "Net-(C41-Pad2)") (class "Default")
      (node (ref "C41") (pin "2") (pinfunction "2_2") (pintype "passive"))
      (node (ref "C43") (pin "2") (pinfunction "2_2") (pintype "passive"))
      (node (ref "JP9") (pin "1") (pinfunction "1_1") (pintype "passive"))
      (node (ref "JP9") (pin "3") (pinfunction "3_3") (pintype "passive"))
      (node (ref "JP9") (pin "5") (pinfunction "5_5") (pintype "passive"))
    )
    (net (code "36") (name "Net-(C42-Pad1)") (class "Default")
      (node (ref "C42") (pin "1") (pinfunction "1_1") (pintype "passive"))
      (node (ref "C46") (pin "1") (pinfunction "1_1") (pintype "passive"))
      (node (ref "C48") (pin "1") (pinfunction "1_1") (pintype "passive"))
      (node (ref "R27") (pin "2") (pinfunction "2_2") (pintype "passive"))
      (node (ref "X1") (pin "1") (pinfunction "1_1") (pintype "passive"))
    )
    (net (code "37") (name "Net-(C46-Pad2)") (class "Default")
      (node (ref "C46") (pin "2") (pinfunction "2_2") (pintype "passive"))
      (node (ref "C48") (pin "2") (pinfunction "2_2") (pintype "passive"))
      (node (ref "JP8") (pin "1") (pinfunction "1_1") (pintype "passive"))
      (node (ref "JP8") (pin "3") (pinfunction "3_3") (pintype "passive"))
      (node (ref "JP8") (pin "5") (pinfunction "5_5") (pintype "passive"))
    )
    (net (code "38") (name "Net-(IC1-WP)") (class "Default")
      (node (ref "IC1") (pin "7") (pinfunction "WP_7") (pintype "input"))
      (node (ref "JP4") (pin "2") (pinfunction "2_2") (pintype "passive"))
    )
    (net (code "39") (name "Net-(IC3A-+IN)") (class "Default")
      (node (ref "C31") (pin "1") (pinfunction "1_1") (pintype "passive"))
      (node (ref "IC3") (pin "3") (pinfunction "+IN_3") (pintype "input"))
      (node (ref "R15") (pin "2") (pinfunction "2_2") (pintype "passive"))
    )
    (net (code "40") (name "Net-(IC3A--IN)") (class "Default")
      (node (ref "C22") (pin "1") (pinfunction "1_1") (pintype "passive"))
      (node (ref "C26") (pin "1") (pinfunction "1_1") (pintype "passive"))
      (node (ref "C29") (pin "2") (pinfunction "2_2") (pintype "passive"))
      (node (ref "IC3") (pin "1") (pinfunction "OUT_1") (pintype "output"))
      (node (ref "IC3") (pin "2") (pinfunction "-IN_2") (pintype "input"))
    )
    (net (code "41") (name "Net-(IC3B-+IN)") (class "Default")
      (node (ref "C27") (pin "1") (pinfunction "1_1") (pintype "passive"))
      (node (ref "IC3") (pin "5") (pinfunction "+IN_5") (pintype "input"))
      (node (ref "R10") (pin "2") (pinfunction "2_2") (pintype "passive"))
    )
    (net (code "42") (name "Net-(IC3B--IN)") (class "Default")
      (node (ref "C21") (pin "1") (pinfunction "1_1") (pintype "passive"))
      (node (ref "C25") (pin "2") (pinfunction "2_2") (pintype "passive"))
      (node (ref "C47") (pin "1") (pinfunction "1_1") (pintype "passive"))
      (node (ref "IC3") (pin "6") (pinfunction "-IN_6") (pintype "input"))
      (node (ref "IC3") (pin "7") (pinfunction "OUT_7") (pintype "output"))
    )
    (net (code "43") (name "Net-(IC3C-+IN)") (class "Default")
      (node (ref "C39") (pin "1") (pinfunction "1_1") (pintype "passive"))
      (node (ref "IC3") (pin "10") (pinfunction "+IN_10") (pintype "input"))
      (node (ref "R23") (pin "2") (pinfunction "2_2") (pintype "passive"))
    )
    (net (code "44") (name "Net-(IC3C--IN)") (class "Default")
      (node (ref "C34") (pin "1") (pinfunction "1_1") (pintype "passive"))
      (node (ref "C37") (pin "2") (pinfunction "2_2") (pintype "passive"))
      (node (ref "C38") (pin "1") (pinfunction "1_1") (pintype "passive"))
      (node (ref "IC3") (pin "8") (pinfunction "OUT_8") (pintype "output"))
      (node (ref "IC3") (pin "9") (pinfunction "-IN_9") (pintype "input"))
    )
    (net (code "45") (name "Net-(IC3D-+IN)") (class "Default")
      (node (ref "C35") (pin "1") (pinfunction "1_1") (pintype "passive"))
      (node (ref "IC3") (pin "12") (pinfunction "+IN_12") (pintype "input"))
      (node (ref "R19") (pin "2") (pinfunction "2_2") (pintype "passive"))
    )
    (net (code "46") (name "Net-(IC3D--IN)") (class "Default")
      (node (ref "C23") (pin "1") (pinfunction "1_1") (pintype "passive"))
      (node (ref "C30") (pin "1") (pinfunction "1_1") (pintype "passive"))
      (node (ref "C33") (pin "2") (pinfunction "2_2") (pintype "passive"))
      (node (ref "IC3") (pin "13") (pinfunction "-IN_13") (pintype "input"))
      (node (ref "IC3") (pin "14") (pinfunction "OUT_14") (pintype "output"))
    )
    (net (code "47") (name "Net-(JP8-Pad2)") (class "Default")
      (node (ref "JP8") (pin "2") (pinfunction "2_2") (pintype "passive"))
      (node (ref "R26") (pin "1") (pinfunction "1_1") (pintype "passive"))
    )
    (net (code "48") (name "Net-(JP8-Pad4)") (class "Default")
      (node (ref "JP8") (pin "4") (pinfunction "4_4") (pintype "passive"))
      (node (ref "R30") (pin "1") (pinfunction "1_1") (pintype "passive"))
    )
    (net (code "49") (name "Net-(JP8-Pad6)") (class "Default")
      (node (ref "JP8") (pin "6") (pinfunction "6_6") (pintype "passive"))
      (node (ref "R31") (pin "1") (pinfunction "1_1") (pintype "passive"))
    )
    (net (code "50") (name "Net-(JP9-Pad2)") (class "Default")
      (node (ref "JP9") (pin "2") (pinfunction "2_2") (pintype "passive"))
      (node (ref "R28") (pin "1") (pinfunction "1_1") (pintype "passive"))
    )
    (net (code "51") (name "Net-(JP9-Pad4)") (class "Default")
      (node (ref "JP9") (pin "4") (pinfunction "4_4") (pintype "passive"))
      (node (ref "R32") (pin "1") (pinfunction "1_1") (pintype "passive"))
    )
    (net (code "52") (name "Net-(JP9-Pad6)") (class "Default")
      (node (ref "JP9") (pin "6") (pinfunction "6_6") (pintype "passive"))
      (node (ref "R33") (pin "1") (pinfunction "1_1") (pintype "passive"))
    )
    (net (code "53") (name "Net-(LED1-PadA)") (class "Default")
      (node (ref "LED1") (pin "A") (pinfunction "A_A") (pintype "passive"))
      (node (ref "R8") (pin "1") (pinfunction "1_1") (pintype "passive"))
    )
    (net (code "54") (name "Net-(Q2-D)") (class "Default")
      (node (ref "JP3") (pin "16") (pinfunction "16_16") (pintype "passive"))
      (node (ref "Q2") (pin "1") (pinfunction "D_1") (pintype "passive"))
      (node (ref "R35") (pin "1") (pinfunction "1_1") (pintype "passive"))
    )
    (net (code "55") (name "Net-(Q3-D)") (class "Default")
      (node (ref "JP3") (pin "17") (pinfunction "17_17") (pintype "passive"))
      (node (ref "Q3") (pin "1") (pinfunction "D_1") (pintype "passive"))
      (node (ref "R36") (pin "1") (pinfunction "1_1") (pintype "passive"))
    )
    (net (code "56") (name "Net-(Q4-D)") (class "Default")
      (node (ref "JP3") (pin "15") (pinfunction "15_15") (pintype "passive"))
      (node (ref "Q4") (pin "1") (pinfunction "D_1") (pintype "passive"))
      (node (ref "R37") (pin "1") (pinfunction "1_1") (pintype "passive"))
    )
    (net (code "57") (name "Net-(Q5-D)") (class "Default")
      (node (ref "JP3") (pin "14") (pinfunction "14_14") (pintype "passive"))
      (node (ref "Q5") (pin "1") (pinfunction "D_1") (pintype "passive"))
      (node (ref "R38") (pin "1") (pinfunction "1_1") (pintype "passive"))
    )
    (net (code "58") (name "Net-(T1-B)") (class "Default")
      (node (ref "R1") (pin "1") (pinfunction "1_1") (pintype "passive"))
      (node (ref "T1") (pin "1") (pinfunction "B_1") (pintype "passive"))
      (node (ref "U$1") (pin "17") (pinfunction "VDRIVE_17") (pintype "bidirectional"))
    )
    (net (code "59") (name "Net-(U$1-ADC0)") (class "Default")
      (node (ref "R26") (pin "2") (pinfunction "2_2") (pintype "passive"))
      (node (ref "R30") (pin "2") (pinfunction "2_2") (pintype "passive"))
      (node (ref "R31") (pin "2") (pinfunction "2_2") (pintype "passive"))
      (node (ref "U$1") (pin "2") (pinfunction "ADC0_2") (pintype "bidirectional"))
    )
    (net (code "60") (name "Net-(U$1-ADC1)") (class "Default")
      (node (ref "R28") (pin "2") (pinfunction "2_2") (pintype "passive"))
      (node (ref "R32") (pin "2") (pinfunction "2_2") (pintype "passive"))
      (node (ref "R33") (pin "2") (pinfunction "2_2") (pintype "passive"))
      (node (ref "U$1") (pin "4") (pinfunction "ADC1_4") (pintype "bidirectional"))
    )
    (net (code "61") (name "Net-(U$1-ADC_RES)") (class "Default")
      (node (ref "R2") (pin "2") (pinfunction "2_2") (pintype "passive"))
      (node (ref "U$1") (pin "3") (pinfunction "ADC_RES_3") (pintype "bidirectional"))
    )
    (net (code "62") (name "Net-(U$1-CM)") (class "Default")
      (node (ref "C12") (pin "1") (pinfunction "1_1") (pintype "passive"))
      (node (ref "C13") (pin "+") (pinfunction "+_+") (pintype "passive"))
      (node (ref "U$1") (pin "40") (pinfunction "CM_40") (pintype "bidirectional"))
    )
    (net (code "63") (name "Net-(U$1-FILTA)") (class "Default")
      (node (ref "C15") (pin "1") (pinfunction "1_1") (pintype "passive"))
      (node (ref "C16") (pin "+") (pinfunction "+_+") (pintype "passive"))
      (node (ref "U$1") (pin "47") (pinfunction "FILTA_47") (pintype "bidirectional"))
    )
    (net (code "64") (name "Net-(U$1-FILTD)") (class "Default")
      (node (ref "C1") (pin "1") (pinfunction "1_1") (pintype "passive"))
      (node (ref "C2") (pin "+") (pinfunction "+_+") (pintype "passive"))
      (node (ref "U$1") (pin "41") (pinfunction "FILTD_41") (pintype "bidirectional"))
    )
    (net (code "65") (name "Net-(U$1-MCLOCKI)") (class "Default")
      (node (ref "JP1") (pin "2") (pinfunction "2_2") (pintype "passive"))
      (node (ref "U$1") (pin "32") (pinfunction "MCLOCKI_32") (pintype "bidirectional"))
    )
    (net (code "66") (name "Net-(U$1-OSCO)") (class "Default")
      (node (ref "R6") (pin "1") (pinfunction "1_1") (pintype "passive"))
      (node (ref "U$1") (pin "31") (pinfunction "OSCO_31") (pintype "bidirectional"))
    )
    (net (code "67") (name "Net-(U$1-PLL_LF)") (class "Default")
      (node (ref "C19") (pin "2") (pinfunction "2_2") (pintype "passive"))
      (node (ref "C20") (pin "2") (pinfunction "2_2") (pintype "passive"))
      (node (ref "U$1") (pin "35") (pinfunction "PLL_LF_35") (pintype "bidirectional"))
    )
    (net (code "68") (name "Net-(U$1-VOUT0)") (class "Default")
      (node (ref "R9") (pin "1") (pinfunction "1_1") (pintype "passive"))
      (node (ref "U$1") (pin "46") (pinfunction "VOUT0_46") (pintype "bidirectional"))
    )
    (net (code "69") (name "Net-(U$1-VOUT1)") (class "Default")
      (node (ref "R14") (pin "1") (pinfunction "1_1") (pintype "passive"))
      (node (ref "U$1") (pin "45") (pinfunction "VOUT1_45") (pintype "bidirectional"))
    )
    (net (code "70") (name "Net-(U$1-VOUT2)") (class "Default")
      (node (ref "R18") (pin "1") (pinfunction "1_1") (pintype "passive"))
      (node (ref "U$1") (pin "44") (pinfunction "VOUT2_44") (pintype "bidirectional"))
    )
    (net (code "71") (name "Net-(U$1-VOUT3)") (class "Default")
      (node (ref "R22") (pin "1") (pinfunction "1_1") (pintype "passive"))
      (node (ref "U$1") (pin "43") (pinfunction "VOUT3_43") (pintype "bidirectional"))
    )
    (net (code "72") (name "SCL") (class "Default")
      (node (ref "IC1") (pin "6") (pinfunction "SCL_6") (pintype "input"))
      (node (ref "JP2") (pin "15") (pinfunction "15_15") (pintype "passive"))
      (node (ref "Q4") (pin "3") (pinfunction "S_3") (pintype "passive"))
      (node (ref "R4") (pin "1") (pinfunction "1_1") (pintype "passive"))
      (node (ref "SV2") (pin "1") (pinfunction "1_1") (pintype "passive"))
      (node (ref "U$1") (pin "23") (pinfunction "SCL/CCLK_23") (pintype "bidirectional"))
    )
    (net (code "73") (name "SDA") (class "Default")
      (node (ref "IC1") (pin "5") (pinfunction "SDA_5") (pintype "bidirectional"))
      (node (ref "JP2") (pin "12") (pinfunction "12_12") (pintype "passive"))
      (node (ref "Q5") (pin "3") (pinfunction "S_3") (pintype "passive"))
      (node (ref "R5") (pin "1") (pinfunction "1_1") (pintype "passive"))
      (node (ref "SV2") (pin "3") (pinfunction "3_3") (pintype "passive"))
      (node (ref "U$1") (pin "22") (pinfunction "SDA/COUT_22") (pintype "bidirectional"))
    )
    (net (code "74") (name "SDATA_IN") (class "Default")
      (node (ref "JP2") (pin "7") (pinfunction "7_7") (pintype "passive"))
      (node (ref "U$1") (pin "11") (pinfunction "MP0_11") (pintype "bidirectional"))
    )
    (net (code "75") (name "VIN") (class "Default")
      (node (ref "C49") (pin "+") (pinfunction "+_+") (pintype "passive"))
      (node (ref "C51") (pin "2") (pinfunction "2_2") (pintype "passive"))
      (node (ref "D1") (pin "C") (pinfunction "C_C") (pintype "passive"))
      (node (ref "D3") (pin "C") (pinfunction "C_C") (pintype "passive"))
      (node (ref "IC2") (pin "3") (pinfunction "VIN_3") (pintype "input"))
      (node (ref "JP12") (pin "1") (pinfunction "1_1") (pintype "passive"))
      (node (ref "JP6") (pin "1") (pinfunction "1_1") (pintype "passive"))
    )
    (net (code "76") (name "WB") (class "Default")
      (node (ref "JP2") (pin "13") (pinfunction "13_13") (pintype "passive"))
      (node (ref "U$1") (pin "20") (pinfunction "ADR1/CDATA/WB_20") (pintype "bidirectional"))
    )
    (net (code "77") (name "WP") (class "Default")
      (node (ref "JP4") (pin "1") (pinfunction "1_1") (pintype "passive"))
      (node (ref "Q2") (pin "3") (pinfunction "S_3") (pintype "passive"))
      (node (ref "R3") (pin "1") (pinfunction "1_1") (pintype "passive"))
      (node (ref "U$1") (pin "21") (pinfunction "CLATCH/WP_21") (pintype "bidirectional"))
    )
    (net (code "78") (name "unconnected-(JP3-Pad1)") (class "Default")
      (node (ref "JP3") (pin "1") (pinfunction "1_1") (pintype "passive"))
    )
    (net (code "79") (name "unconnected-(JP3-Pad2)") (class "Default")
      (node (ref "JP3") (pin "2") (pinfunction "2_2") (pintype "passive"))
    )
    (net (code "80") (name "unconnected-(JP3-Pad3)") (class "Default")
      (node (ref "JP3") (pin "3") (pinfunction "3_3") (pintype "passive"))
    )
    (net (code "81") (name "unconnected-(JP3-Pad4)") (class "Default")
      (node (ref "JP3") (pin "4") (pinfunction "4_4") (pintype "passive"))
    )
    (net (code "82") (name "unconnected-(JP3-Pad5)") (class "Default")
      (node (ref "JP3") (pin "5") (pinfunction "5_5") (pintype "passive"))
    )
    (net (code "83") (name "unconnected-(JP3-Pad7)") (class "Default")
      (node (ref "JP3") (pin "7") (pinfunction "7_7") (pintype "passive"))
    )
    (net (code "84") (name "unconnected-(JP3-Pad8)") (class "Default")
      (node (ref "JP3") (pin "8") (pinfunction "8_8") (pintype "passive"))
    )
    (net (code "85") (name "unconnected-(JP3-Pad9)") (class "Default")
      (node (ref "JP3") (pin "9") (pinfunction "9_9") (pintype "passive"))
    )
    (net (code "86") (name "unconnected-(JP3-Pad10)") (class "Default")
      (node (ref "JP3") (pin "10") (pinfunction "10_10") (pintype "passive"))
    )
    (net (code "87") (name "unconnected-(JP3-Pad11)") (class "Default")
      (node (ref "JP3") (pin "11") (pinfunction "11_11") (pintype "passive"))
    )
    (net (code "88") (name "unconnected-(JP3-Pad12)") (class "Default")
      (node (ref "JP3") (pin "12") (pinfunction "12_12") (pintype "passive"))
    )
    (net (code "89") (name "unconnected-(JP3-Pad13)") (class "Default")
      (node (ref "JP3") (pin "13") (pinfunction "13_13") (pintype "passive"))
    )
    (net (code "90") (name "unconnected-(JP5-Pad1)") (class "Default")
      (node (ref "JP5") (pin "1") (pinfunction "1_1") (pintype "passive"))
    )
    (net (code "91") (name "unconnected-(JP5-Pad2)") (class "Default")
      (node (ref "JP5") (pin "2") (pinfunction "2_2") (pintype "passive"))
    )
    (net (code "92") (name "unconnected-(JP5-Pad3)") (class "Default")
      (node (ref "JP5") (pin "3") (pinfunction "3_3") (pintype "passive"))
    )
    (net (code "93") (name "unconnected-(JP5-Pad5)") (class "Default")
      (node (ref "JP5") (pin "5") (pinfunction "5_5") (pintype "passive"))
    )
    (net (code "94") (name "unconnected-(JP5-Pad7)") (class "Default")
      (node (ref "JP5") (pin "7") (pinfunction "7_7") (pintype "passive"))
    )
    (net (code "95") (name "unconnected-(JP5-Pad8)") (class "Default")
      (node (ref "JP5") (pin "8") (pinfunction "8_8") (pintype "passive"))
    )
    (net (code "96") (name "unconnected-(JP5-Pad9)") (class "Default")
      (node (ref "JP5") (pin "9") (pinfunction "9_9") (pintype "passive"))
    )
    (net (code "97") (name "unconnected-(JP5-Pad10)") (class "Default")
      (node (ref "JP5") (pin "10") (pinfunction "10_10") (pintype "passive"))
    )
    (net (code "98") (name "unconnected-(JP5-Pad11)") (class "Default")
      (node (ref "JP5") (pin "11") (pinfunction "11_11") (pintype "passive"))
    )
    (net (code "99") (name "unconnected-(JP5-Pad12)") (class "Default")
      (node (ref "JP5") (pin "12") (pinfunction "12_12") (pintype "passive"))
    )
    (net (code "100") (name "unconnected-(JP5-Pad13)") (class "Default")
      (node (ref "JP5") (pin "13") (pinfunction "13_13") (pintype "passive"))
    )
    (net (code "101") (name "unconnected-(JP5-Pad14)") (class "Default")
      (node (ref "JP5") (pin "14") (pinfunction "14_14") (pintype "passive"))
    )
    (net (code "102") (name "unconnected-(JP5-Pad15)") (class "Default")
      (node (ref "JP5") (pin "15") (pinfunction "15_15") (pintype "passive"))
    )
    (net (code "103") (name "unconnected-(JP5-Pad16)") (class "Default")
      (node (ref "JP5") (pin "16") (pinfunction "16_16") (pintype "passive"))
    )
    (net (code "104") (name "unconnected-(JP5-Pad17)") (class "Default")
      (node (ref "JP5") (pin "17") (pinfunction "17_17") (pintype "passive"))
    )
    (net (code "105") (name "unconnected-(SV2-Pad2)") (class "Default")
      (node (ref "SV2") (pin "2") (pinfunction "2_2") (pintype "passive"))
    )
    (net (code "106") (name "unconnected-(SV2-Pad5)") (class "Default")
      (node (ref "SV2") (pin "5") (pinfunction "5_5") (pintype "passive"))
    )
    (net (code "107") (name "unconnected-(SV2-Pad7)") (class "Default")
      (node (ref "SV2") (pin "7") (pinfunction "7_7") (pintype "passive"))
    )
    (net (code "108") (name "unconnected-(SV2-Pad8)") (class "Default")
      (node (ref "SV2") (pin "8") (pinfunction "8_8") (pintype "passive"))
    )
    (net (code "109") (name "unconnected-(SV2-Pad9)") (class "Default")
      (node (ref "SV2") (pin "9") (pinfunction "9_9") (pintype "passive"))
    )
  )
)
